# ADC.net
KiCad netlist of a schematic drawn in Altium Designer
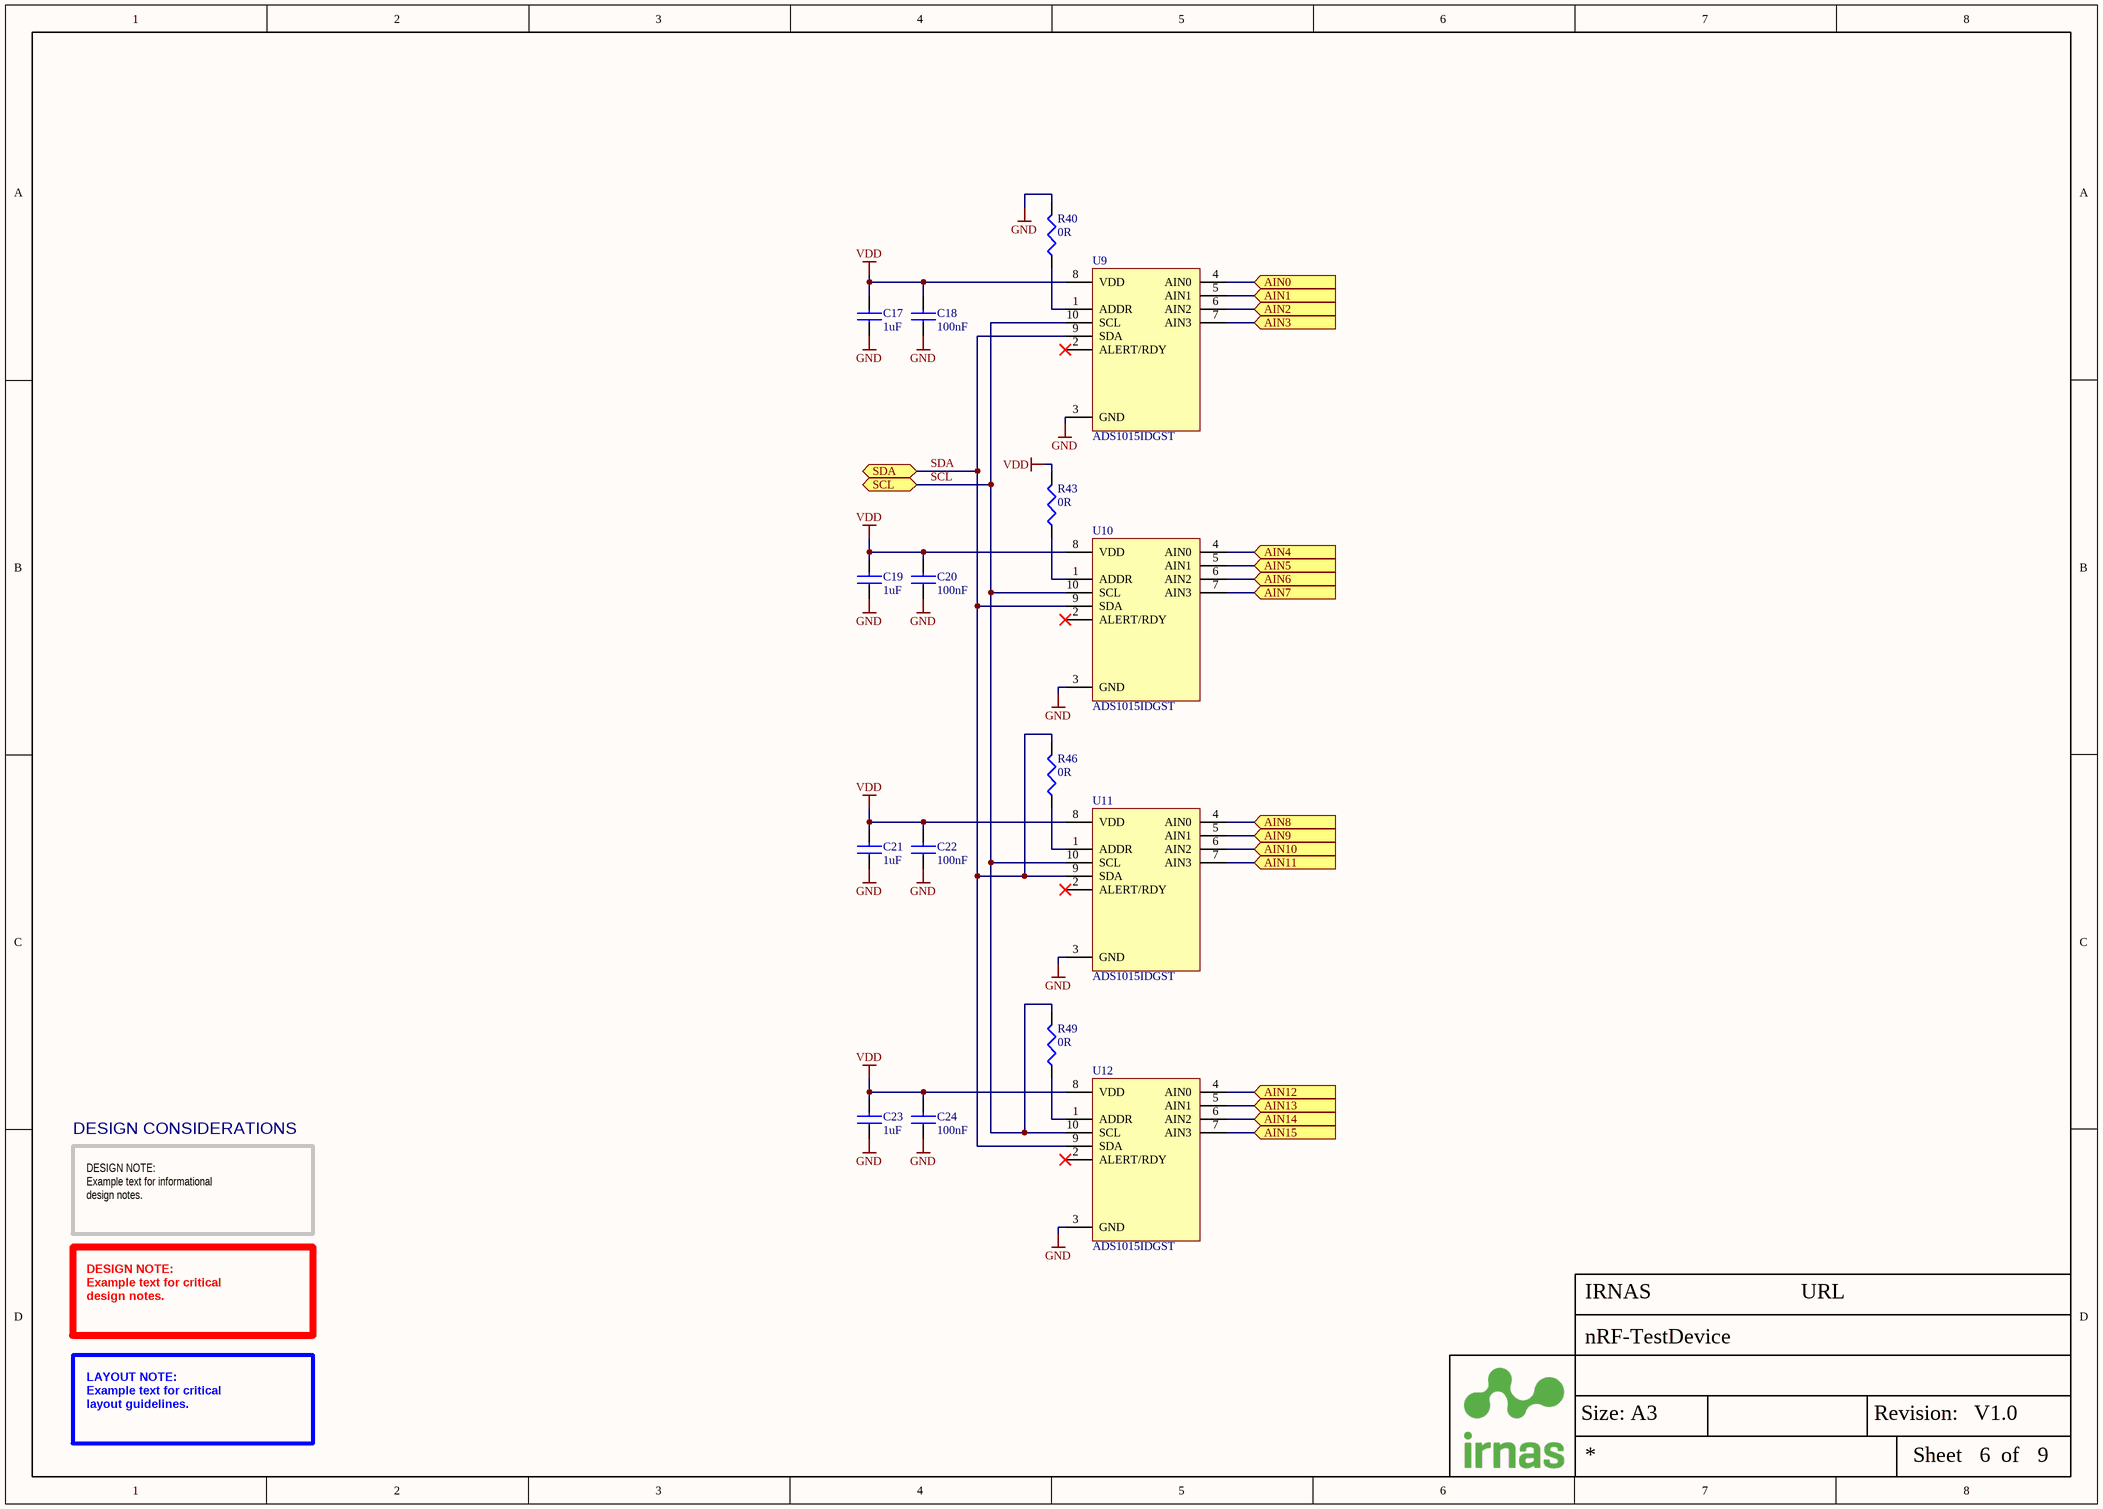
[diagram p0: ADC.SchDoc]

(export (version "E")
  (design (tool "Eeschema 10.0.6"))
  (components
    (comp (ref "C17")
      (value "1uF")
      (footprint "CAP0402")
      (description "CAP CER 1UF 10V 20% X5R 0402")
      (fields
        (field (name "MANUFACTURER") "Murata")
        (field (name "MANUFACTURER PART NUMBER") "GRM155R61A105ME15D")
      )
      (libsource (lib "Passive") (part "C - 1uF/0402"))
    )
    (comp (ref "C18")
      (value "100nF")
      (footprint "CAP0402")
      (fields
        (field (name "MANUFACTURER") "Multicomp")
        (field (name "MANUFACTURER PART NUMBER") "MC0402X104J160CT")
        (field (name "TOLERANCE") "5%")
      )
      (libsource (lib "Passive") (part "C - 100nF/0402"))
    )
    (comp (ref "C19")
      (value "1uF")
      (footprint "CAP0402")
      (description "CAP CER 1UF 10V 20% X5R 0402")
      (fields
        (field (name "MANUFACTURER") "Murata")
        (field (name "MANUFACTURER PART NUMBER") "GRM155R61A105ME15D")
      )
      (libsource (lib "Passive") (part "C - 1uF/0402"))
    )
    (comp (ref "C20")
      (value "100nF")
      (footprint "CAP0402")
      (fields
        (field (name "MANUFACTURER") "Multicomp")
        (field (name "MANUFACTURER PART NUMBER") "MC0402X104J160CT")
        (field (name "TOLERANCE") "5%")
      )
      (libsource (lib "Passive") (part "C - 100nF/0402"))
    )
    (comp (ref "C21")
      (value "1uF")
      (footprint "CAP0402")
      (description "CAP CER 1UF 10V 20% X5R 0402")
      (fields
        (field (name "MANUFACTURER") "Murata")
        (field (name "MANUFACTURER PART NUMBER") "GRM155R61A105ME15D")
      )
      (libsource (lib "Passive") (part "C - 1uF/0402"))
    )
    (comp (ref "C22")
      (value "100nF")
      (footprint "CAP0402")
      (fields
        (field (name "MANUFACTURER") "Multicomp")
        (field (name "MANUFACTURER PART NUMBER") "MC0402X104J160CT")
        (field (name "TOLERANCE") "5%")
      )
      (libsource (lib "Passive") (part "C - 100nF/0402"))
    )
    (comp (ref "C23")
      (value "1uF")
      (footprint "CAP0402")
      (description "CAP CER 1UF 10V 20% X5R 0402")
      (fields
        (field (name "MANUFACTURER") "Murata")
        (field (name "MANUFACTURER PART NUMBER") "GRM155R61A105ME15D")
      )
      (libsource (lib "Passive") (part "C - 1uF/0402"))
    )
    (comp (ref "C24")
      (value "100nF")
      (footprint "CAP0402")
      (fields
        (field (name "MANUFACTURER") "Multicomp")
        (field (name "MANUFACTURER PART NUMBER") "MC0402X104J160CT")
        (field (name "TOLERANCE") "5%")
      )
      (libsource (lib "Passive") (part "C - 100nF/0402"))
    )
    (comp (ref "R40")
      (value "0R")
      (footprint "RES0402")
      (description "RESISTOR, 0402, 0R, ANTI SULFURATION")
      (fields
        (field (name "MANUFACTURER") "Multicomp")
        (field (name "MANUFACTURER PART NUMBER") "MCMR04X000PTL")
      )
      (libsource (lib "Passive") (part "R - 0R/0402"))
    )
    (comp (ref "R43")
      (value "0R")
      (footprint "RES0402")
      (description "RESISTOR, 0402, 0R, ANTI SULFURATION")
      (fields
        (field (name "MANUFACTURER") "Multicomp")
        (field (name "MANUFACTURER PART NUMBER") "MCMR04X000PTL")
      )
      (libsource (lib "Passive") (part "R - 0R/0402"))
    )
    (comp (ref "R46")
      (value "0R")
      (footprint "RES0402")
      (description "RESISTOR, 0402, 0R, ANTI SULFURATION")
      (fields
        (field (name "MANUFACTURER") "Multicomp")
        (field (name "MANUFACTURER PART NUMBER") "MCMR04X000PTL")
      )
      (libsource (lib "Passive") (part "R - 0R/0402"))
    )
    (comp (ref "R49")
      (value "0R")
      (footprint "RES0402")
      (description "RESISTOR, 0402, 0R, ANTI SULFURATION")
      (fields
        (field (name "MANUFACTURER") "Multicomp")
        (field (name "MANUFACTURER PART NUMBER") "MCMR04X000PTL")
      )
      (libsource (lib "Passive") (part "R - 0R/0402"))
    )
    (comp (ref "U9")
      (value "ADS1015IDGST")
      (footprint "VSSOP-10")
      (description "Analogue to Digital Converter, 12 bit, 3.3 kSPS, Differential, Single Ended, I2C, Single")
      (fields (field (name "MANUFACTURER") "TEXAS INSTRUMENTS"))
      (libsource (lib "Active") (part "ADC - ADS1015IDGST"))
    )
    (comp (ref "U10")
      (value "ADS1015IDGST")
      (footprint "VSSOP-10")
      (description "Analogue to Digital Converter, 12 bit, 3.3 kSPS, Differential, Single Ended, I2C, Single")
      (fields (field (name "MANUFACTURER") "TEXAS INSTRUMENTS"))
      (libsource (lib "Active") (part "ADC - ADS1015IDGST"))
    )
    (comp (ref "U11")
      (value "ADS1015IDGST")
      (footprint "VSSOP-10")
      (description "Analogue to Digital Converter, 12 bit, 3.3 kSPS, Differential, Single Ended, I2C, Single")
      (fields (field (name "MANUFACTURER") "TEXAS INSTRUMENTS"))
      (libsource (lib "Active") (part "ADC - ADS1015IDGST"))
    )
    (comp (ref "U12")
      (value "ADS1015IDGST")
      (footprint "VSSOP-10")
      (description "Analogue to Digital Converter, 12 bit, 3.3 kSPS, Differential, Single Ended, I2C, Single")
      (fields (field (name "MANUFACTURER") "TEXAS INSTRUMENTS"))
      (libsource (lib "Active") (part "ADC - ADS1015IDGST"))
    )
  )
  (nets
    (net (code "1") (name "/AIN0") (class "Default")
      (node (ref "U9") (pin "4") (pinfunction "AIN0_4") (pintype "passive"))
    )
    (net (code "2") (name "/AIN1") (class "Default")
      (node (ref "U9") (pin "5") (pinfunction "AIN1_5") (pintype "passive"))
    )
    (net (code "3") (name "/AIN2") (class "Default")
      (node (ref "U9") (pin "6") (pinfunction "AIN2_6") (pintype "passive"))
    )
    (net (code "4") (name "/AIN3") (class "Default")
      (node (ref "U9") (pin "7") (pinfunction "AIN3_7") (pintype "passive"))
    )
    (net (code "5") (name "/AIN4") (class "Default")
      (node (ref "U10") (pin "4") (pinfunction "AIN0_4") (pintype "passive"))
    )
    (net (code "6") (name "/AIN5") (class "Default")
      (node (ref "U10") (pin "5") (pinfunction "AIN1_5") (pintype "passive"))
    )
    (net (code "7") (name "/AIN6") (class "Default")
      (node (ref "U10") (pin "6") (pinfunction "AIN2_6") (pintype "passive"))
    )
    (net (code "8") (name "/AIN7") (class "Default")
      (node (ref "U10") (pin "7") (pinfunction "AIN3_7") (pintype "passive"))
    )
    (net (code "9") (name "/AIN8") (class "Default")
      (node (ref "U11") (pin "4") (pinfunction "AIN0_4") (pintype "passive"))
    )
    (net (code "10") (name "/AIN9") (class "Default")
      (node (ref "U11") (pin "5") (pinfunction "AIN1_5") (pintype "passive"))
    )
    (net (code "11") (name "/AIN10") (class "Default")
      (node (ref "U11") (pin "6") (pinfunction "AIN2_6") (pintype "passive"))
    )
    (net (code "12") (name "/AIN11") (class "Default")
      (node (ref "U11") (pin "7") (pinfunction "AIN3_7") (pintype "passive"))
    )
    (net (code "13") (name "/AIN12") (class "Default")
      (node (ref "U12") (pin "4") (pinfunction "AIN0_4") (pintype "passive"))
    )
    (net (code "14") (name "/AIN13") (class "Default")
      (node (ref "U12") (pin "5") (pinfunction "AIN1_5") (pintype "passive"))
    )
    (net (code "15") (name "/AIN14") (class "Default")
      (node (ref "U12") (pin "6") (pinfunction "AIN2_6") (pintype "passive"))
    )
    (net (code "16") (name "/AIN15") (class "Default")
      (node (ref "U12") (pin "7") (pinfunction "AIN3_7") (pintype "passive"))
    )
    (net (code "17") (name "/SCL") (class "Default")
      (node (ref "R49") (pin "2") (pinfunction "2_2") (pintype "passive"))
      (node (ref "U10") (pin "10") (pinfunction "SCL_10") (pintype "passive"))
      (node (ref "U11") (pin "10") (pinfunction "SCL_10") (pintype "passive"))
      (node (ref "U12") (pin "10") (pinfunction "SCL_10") (pintype "passive"))
      (node (ref "U9") (pin "10") (pinfunction "SCL_10") (pintype "passive"))
    )
    (net (code "18") (name "/SDA") (class "Default")
      (node (ref "R46") (pin "2") (pinfunction "2_2") (pintype "passive"))
      (node (ref "U10") (pin "9") (pinfunction "SDA_9") (pintype "passive"))
      (node (ref "U11") (pin "9") (pinfunction "SDA_9") (pintype "passive"))
      (node (ref "U12") (pin "9") (pinfunction "SDA_9") (pintype "passive"))
      (node (ref "U9") (pin "9") (pinfunction "SDA_9") (pintype "passive"))
    )
    (net (code "19") (name "GND") (class "Default")
      (node (ref "C17") (pin "1") (pinfunction "1_1") (pintype "passive"))
      (node (ref "C18") (pin "1") (pinfunction "1_1") (pintype "passive"))
      (node (ref "C19") (pin "1") (pinfunction "1_1") (pintype "passive"))
      (node (ref "C20") (pin "1") (pinfunction "1_1") (pintype "passive"))
      (node (ref "C21") (pin "1") (pinfunction "1_1") (pintype "passive"))
      (node (ref "C22") (pin "1") (pinfunction "1_1") (pintype "passive"))
      (node (ref "C23") (pin "1") (pinfunction "1_1") (pintype "passive"))
      (node (ref "C24") (pin "1") (pinfunction "1_1") (pintype "passive"))
      (node (ref "R40") (pin "2") (pinfunction "2_2") (pintype "passive"))
      (node (ref "U10") (pin "3") (pinfunction "GND_3") (pintype "passive"))
      (node (ref "U11") (pin "3") (pinfunction "GND_3") (pintype "passive"))
      (node (ref "U12") (pin "3") (pinfunction "GND_3") (pintype "passive"))
      (node (ref "U9") (pin "3") (pinfunction "GND_3") (pintype "passive"))
    )
    (net (code "20") (name "Net-(U9-ADDR)") (class "Default")
      (node (ref "R40") (pin "1") (pinfunction "1_1") (pintype "passive"))
      (node (ref "U9") (pin "1") (pinfunction "ADDR_1") (pintype "passive"))
    )
    (net (code "21") (name "Net-(U10-ADDR)") (class "Default")
      (node (ref "R43") (pin "1") (pinfunction "1_1") (pintype "passive"))
      (node (ref "U10") (pin "1") (pinfunction "ADDR_1") (pintype "passive"))
    )
    (net (code "22") (name "Net-(U11-ADDR)") (class "Default")
      (node (ref "R46") (pin "1") (pinfunction "1_1") (pintype "passive"))
      (node (ref "U11") (pin "1") (pinfunction "ADDR_1") (pintype "passive"))
    )
    (net (code "23") (name "Net-(U12-ADDR)") (class "Default")
      (node (ref "R49") (pin "1") (pinfunction "1_1") (pintype "passive"))
      (node (ref "U12") (pin "1") (pinfunction "ADDR_1") (pintype "passive"))
    )
    (net (code "24") (name "VDD") (class "Default")
      (node (ref "C17") (pin "2") (pinfunction "2_2") (pintype "passive"))
      (node (ref "C18") (pin "2") (pinfunction "2_2") (pintype "passive"))
      (node (ref "C19") (pin "2") (pinfunction "2_2") (pintype "passive"))
      (node (ref "C20") (pin "2") (pinfunction "2_2") (pintype "passive"))
      (node (ref "C21") (pin "2") (pinfunction "2_2") (pintype "passive"))
      (node (ref "C22") (pin "2") (pinfunction "2_2") (pintype "passive"))
      (node (ref "C23") (pin "2") (pinfunction "2_2") (pintype "passive"))
      (node (ref "C24") (pin "2") (pinfunction "2_2") (pintype "passive"))
      (node (ref "R43") (pin "2") (pinfunction "2_2") (pintype "passive"))
      (node (ref "U10") (pin "8") (pinfunction "VDD_8") (pintype "passive"))
      (node (ref "U11") (pin "8") (pinfunction "VDD_8") (pintype "passive"))
      (node (ref "U12") (pin "8") (pinfunction "VDD_8") (pintype "passive"))
      (node (ref "U9") (pin "8") (pinfunction "VDD_8") (pintype "passive"))
    )
    (net (code "25") (name "unconnected-(U9-ALERT{slash}RDY-Pad2)") (class "Default")
      (node (ref "U9") (pin "2") (pinfunction "ALERT/RDY_2") (pintype "passive+no_connect"))
    )
    (net (code "26") (name "unconnected-(U10-ALERT{slash}RDY-Pad2)") (class "Default")
      (node (ref "U10") (pin "2") (pinfunction "ALERT/RDY_2") (pintype "passive+no_connect"))
    )
    (net (code "27") (name "unconnected-(U11-ALERT{slash}RDY-Pad2)") (class "Default")
      (node (ref "U11") (pin "2") (pinfunction "ALERT/RDY_2") (pintype "passive+no_connect"))
    )
    (net (code "28") (name "unconnected-(U12-ALERT{slash}RDY-Pad2)") (class "Default")
      (node (ref "U12") (pin "2") (pinfunction "ALERT/RDY_2") (pintype "passive+no_connect"))
    )
  )
)
